# master-v2.net
KiCad netlist of a schematic drawn in EAGLE
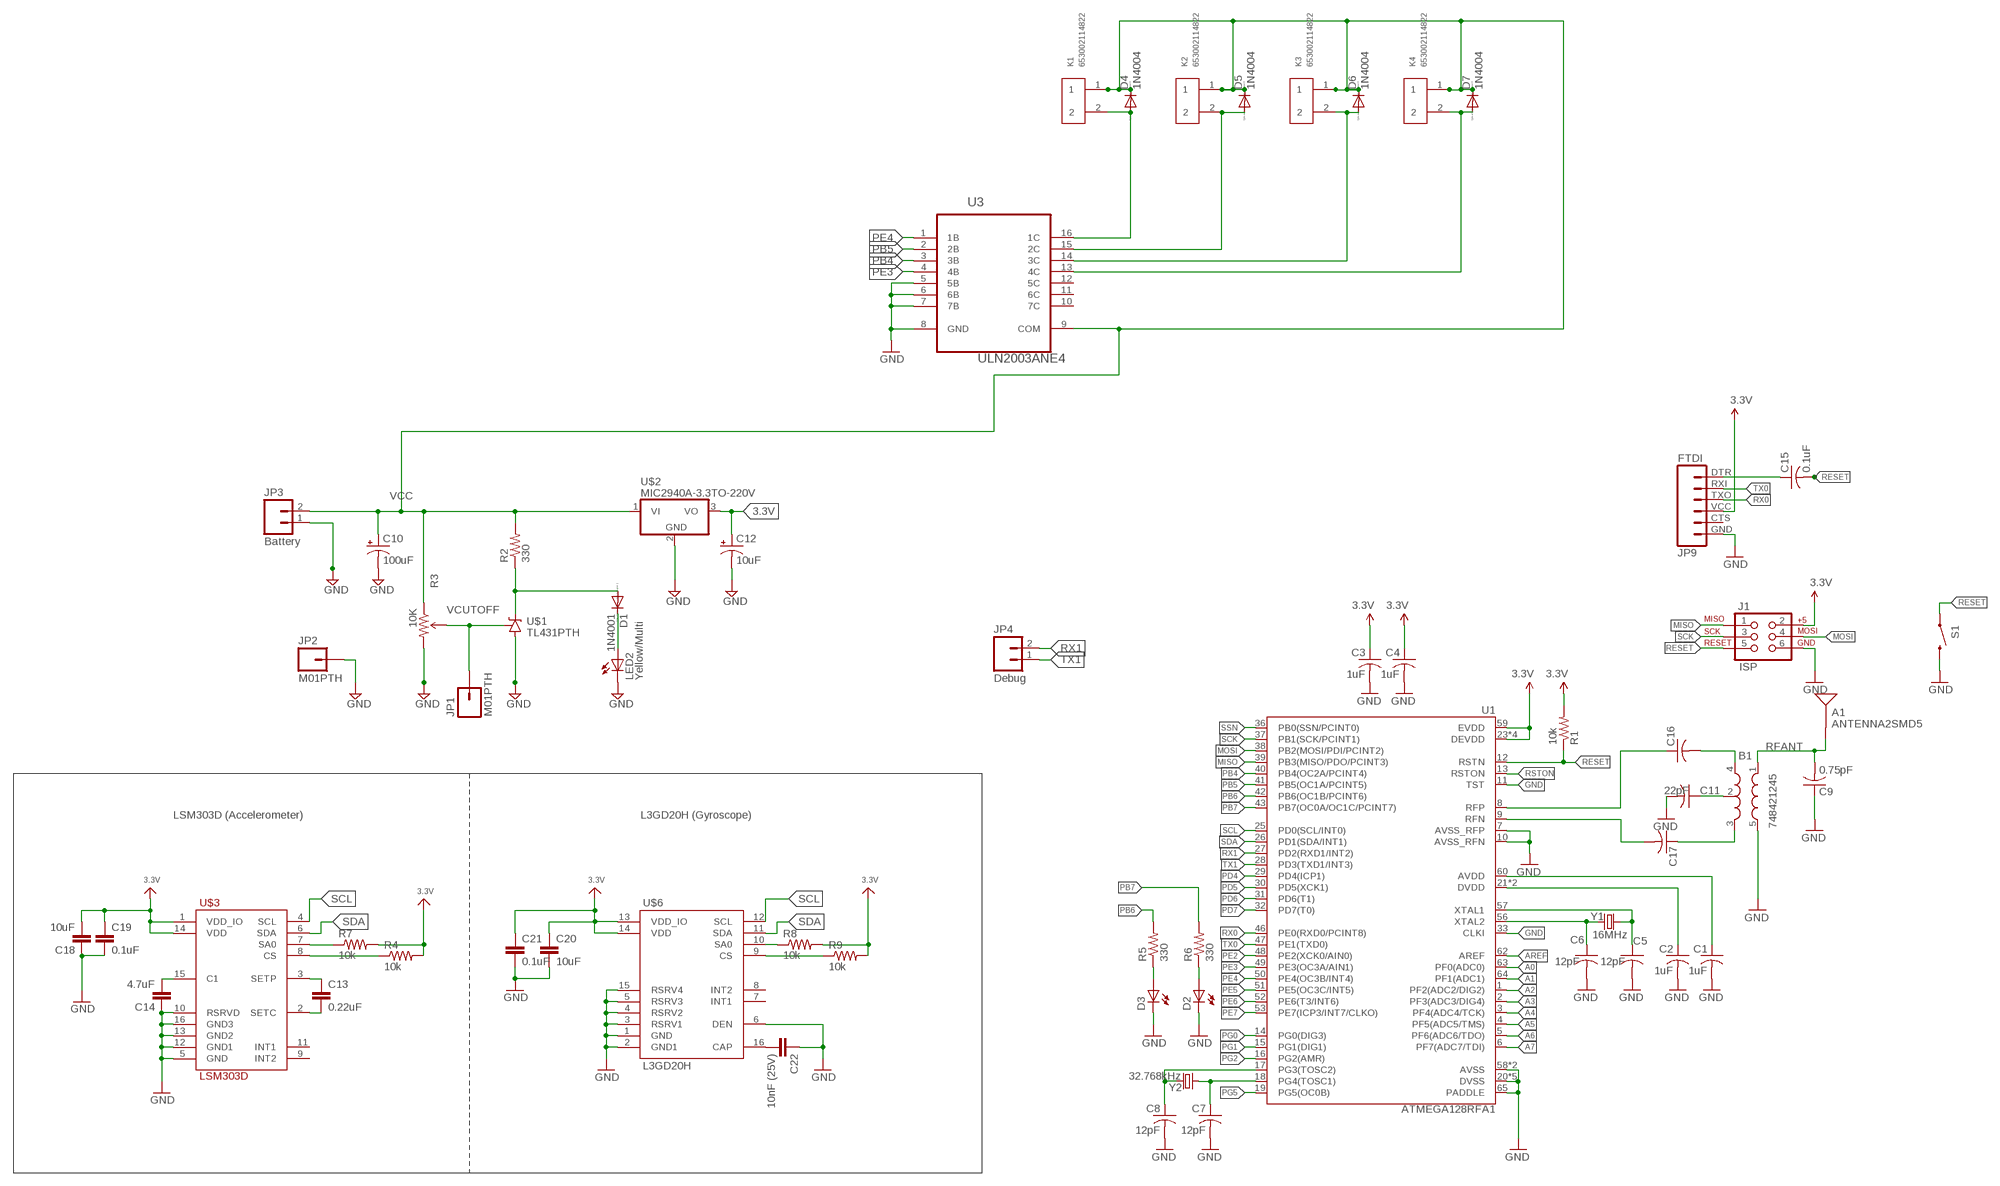
[diagram p0: schematic, sheet 1]

(export (version "E")
  (design (tool "Eeschema 10.0.6"))
  (components
    (comp (ref "A1")
      (value "ANTENNA2SMD5")
      (footprint "eagle-import:ANTENNA-CHIP5")
      (libsource (lib "eagle-import") (part "ANTENNA2SMD5"))
    )
    (comp (ref "B1")
      (value "748421245")
      (footprint "eagle-import:BALUN")
      (libsource (lib "eagle-import") (part "BALUN0805"))
    )
    (comp (ref "C1")
      (value "1uF")
      (footprint "eagle-import:C0805")
      (libsource (lib "eagle-import") (part "C-USC0805"))
    )
    (comp (ref "C2")
      (value "1uF")
      (footprint "eagle-import:C0805")
      (libsource (lib "eagle-import") (part "C-USC0805"))
    )
    (comp (ref "C3")
      (value "1uF")
      (footprint "eagle-import:C0805")
      (libsource (lib "eagle-import") (part "C-USC0805"))
    )
    (comp (ref "C4")
      (value "1uF")
      (footprint "eagle-import:C0805")
      (libsource (lib "eagle-import") (part "C-USC0805"))
    )
    (comp (ref "C5")
      (value "12pF")
      (footprint "eagle-import:C0805")
      (libsource (lib "eagle-import") (part "C-USC0805"))
    )
    (comp (ref "C6")
      (value "12pF")
      (footprint "eagle-import:C0805")
      (libsource (lib "eagle-import") (part "C-USC0805"))
    )
    (comp (ref "C7")
      (value "12pF")
      (footprint "eagle-import:C0805")
      (libsource (lib "eagle-import") (part "C-USC0805"))
    )
    (comp (ref "C8")
      (value "12pF")
      (footprint "eagle-import:C0805")
      (libsource (lib "eagle-import") (part "C-USC0805"))
    )
    (comp (ref "C9")
      (value "0.75pF")
      (footprint "eagle-import:C0805")
      (libsource (lib "eagle-import") (part "C-USC0805"))
    )
    (comp (ref "C10")
      (value "100uF")
      (footprint "eagle-import:E3,5-8")
      (libsource (lib "eagle-import") (part "CPOL-USE3.5-8"))
    )
    (comp (ref "C11")
      (value "22pF")
      (footprint "eagle-import:C0805")
      (libsource (lib "eagle-import") (part "C-USC0805"))
    )
    (comp (ref "C12")
      (value "10uF")
      (footprint "eagle-import:E2,5-5")
      (libsource (lib "eagle-import") (part "CPOL-USE2.5-5"))
    )
    (comp (ref "C13")
      (value "0.22uF")
      (footprint "eagle-import:0805")
      (libsource (lib "eagle-import") (part "CAP0805"))
    )
    (comp (ref "C14")
      (value "4.7uF")
      (footprint "eagle-import:0805")
      (libsource (lib "eagle-import") (part "CAP0805"))
    )
    (comp (ref "C15")
      (value "0.1uF")
      (footprint "eagle-import:C0805")
      (libsource (lib "eagle-import") (part "C-USC0805"))
    )
    (comp (ref "C16")
      (value "C-USC0805")
      (footprint "eagle-import:C0805")
      (libsource (lib "eagle-import") (part "C-USC0805"))
    )
    (comp (ref "C17")
      (value "C-USC0805")
      (footprint "eagle-import:C0805")
      (libsource (lib "eagle-import") (part "C-USC0805"))
    )
    (comp (ref "C18")
      (value "10uF")
      (footprint "eagle-import:0805")
      (libsource (lib "eagle-import") (part "CAP0805"))
    )
    (comp (ref "C19")
      (value "0.1uF")
      (footprint "eagle-import:0805")
      (libsource (lib "eagle-import") (part "CAP0805"))
    )
    (comp (ref "C20")
      (value "10uF")
      (footprint "eagle-import:0805")
      (libsource (lib "eagle-import") (part "CAP0805"))
    )
    (comp (ref "C21")
      (value "0.1uF")
      (footprint "eagle-import:0805")
      (libsource (lib "eagle-import") (part "CAP0805"))
    )
    (comp (ref "C22")
      (value "10nF (25V)")
      (footprint "eagle-import:0805")
      (libsource (lib "eagle-import") (part "CAP0805"))
    )
    (comp (ref "D1")
      (value "1N4001")
      (footprint "eagle-import:DO41-10")
      (libsource (lib "eagle-import") (part "1N4004"))
    )
    (comp (ref "D2")
      (value "LED5MM")
      (footprint "eagle-import:LED5MM")
      (libsource (lib "eagle-import") (part "LED5MM"))
    )
    (comp (ref "D3")
      (value "LED5MM")
      (footprint "eagle-import:LED5MM")
      (libsource (lib "eagle-import") (part "LED5MM"))
    )
    (comp (ref "D4")
      (value "1N4004")
      (footprint "eagle-import:DO41-10")
      (fields (field (name "MF") "NTE ELECTRONICS"))
      (libsource (lib "eagle-import") (part "1N4004"))
    )
    (comp (ref "D5")
      (value "1N4004")
      (footprint "eagle-import:DO41-10")
      (fields (field (name "MF") "NTE ELECTRONICS"))
      (libsource (lib "eagle-import") (part "1N4004"))
    )
    (comp (ref "D6")
      (value "1N4004")
      (footprint "eagle-import:DO41-10")
      (fields (field (name "MF") "NTE ELECTRONICS"))
      (libsource (lib "eagle-import") (part "1N4004"))
    )
    (comp (ref "D7")
      (value "1N4004")
      (footprint "eagle-import:DO41-10")
      (fields (field (name "MF") "NTE ELECTRONICS"))
      (libsource (lib "eagle-import") (part "1N4004"))
    )
    (comp (ref "J1")
      (value "ISP")
      (footprint "eagle-import:2X3-NS")
      (libsource (lib "eagle-import") (part "AVR_SPI_PRG_6NS"))
    )
    (comp (ref "JP1")
      (value "M01PTH")
      (footprint "eagle-import:1X01")
      (libsource (lib "eagle-import") (part "M01PTH"))
    )
    (comp (ref "JP2")
      (value "M01PTH")
      (footprint "eagle-import:1X01")
      (libsource (lib "eagle-import") (part "M01PTH"))
    )
    (comp (ref "JP3")
      (value "Battery")
      (footprint "eagle-import:1X02")
      (libsource (lib "eagle-import") (part "M02PTH"))
    )
    (comp (ref "JP4")
      (value "Debug")
      (footprint "eagle-import:1X02")
      (libsource (lib "eagle-import") (part "M02PTH"))
    )
    (comp (ref "JP9")
      (value "FTDI")
      (footprint "eagle-import:FTDI_BASIC")
      (libsource (lib "eagle-import") (part "FTDI_BASICPTH"))
    )
    (comp (ref "K1")
      (value "653002114822")
      (footprint "eagle-import:653002114822")
      (libsource (lib "eagle-import") (part "653002114822"))
    )
    (comp (ref "K2")
      (value "653002114822")
      (footprint "eagle-import:653002114822")
      (libsource (lib "eagle-import") (part "653002114822"))
    )
    (comp (ref "K3")
      (value "653002114822")
      (footprint "eagle-import:653002114822")
      (libsource (lib "eagle-import") (part "653002114822"))
    )
    (comp (ref "K4")
      (value "653002114822")
      (footprint "eagle-import:653002114822")
      (libsource (lib "eagle-import") (part "653002114822"))
    )
    (comp (ref "LED2")
      (value "Yellow/Multi")
      (footprint "eagle-import:LED5MM")
      (libsource (lib "eagle-import") (part "SparkFun_LED5MM"))
    )
    (comp (ref "R1")
      (value "10k")
      (footprint "eagle-import:R0805")
      (libsource (lib "eagle-import") (part "R-US_R0805"))
    )
    (comp (ref "R2")
      (value "330")
      (footprint "eagle-import:AXIAL-0.3")
      (libsource (lib "eagle-import") (part "RESISTORAXIAL-0.3"))
    )
    (comp (ref "R3")
      (value "10K")
      (footprint "eagle-import:3386U")
      (fields (field (name "CREATOR") "Brandon") (field (name "REVIEWER1") "Chris"))
      (libsource (lib "eagle-import") (part "TRIMPOT-PTH-KNOB"))
    )
    (comp (ref "R4")
      (value "10k")
      (footprint "eagle-import:0805")
      (libsource (lib "eagle-import") (part "SparkFun-Passives_RESISTOR0805-RES"))
    )
    (comp (ref "R5")
      (value "330")
      (footprint "eagle-import:R0805")
      (libsource (lib "eagle-import") (part "R-US_R0805"))
    )
    (comp (ref "R6")
      (value "330")
      (footprint "eagle-import:R0805")
      (libsource (lib "eagle-import") (part "R-US_R0805"))
    )
    (comp (ref "R7")
      (value "10k")
      (footprint "eagle-import:0805")
      (libsource (lib "eagle-import") (part "SparkFun-Passives_RESISTOR0805-RES"))
    )
    (comp (ref "R8")
      (value "10k")
      (footprint "eagle-import:0805")
      (libsource (lib "eagle-import") (part "SparkFun-Passives_RESISTOR0805-RES"))
    )
    (comp (ref "R9")
      (value "10k")
      (footprint "eagle-import:0805")
      (libsource (lib "eagle-import") (part "SparkFun-Passives_RESISTOR0805-RES"))
    )
    (comp (ref "S1")
      (value "SWITCH-MOMENTARY-2SMD")
      (footprint "eagle-import:TACTILE_SWITCH_SMD")
      (libsource (lib "eagle-import") (part "SWITCH-MOMENTARY-2SMD"))
    )
    (comp (ref "U$1")
      (value "TL431PTH")
      (footprint "eagle-import:TO-92")
      (libsource (lib "eagle-import") (part "TL431PTH"))
    )
    (comp (ref "U$2")
      (value "MIC2940A-3.3TO-220V")
      (footprint "eagle-import:TO-220V")
      (libsource (lib "eagle-import") (part "MIC2940A-3.3TO-220V"))
    )
    (comp (ref "U$3")
      (value "LSM303D")
      (footprint "eagle-import:LGA16_3X3MM")
      (libsource (lib "eagle-import") (part "LSM303D"))
    )
    (comp (ref "U$6")
      (value "L3GD20H")
      (footprint "eagle-import:LGA16_3X3MM")
      (libsource (lib "eagle-import") (part "L3GD20H"))
    )
    (comp (ref "U1")
      (value "ATMEGA128RFA1")
      (footprint "eagle-import:QFN-64")
      (libsource (lib "eagle-import") (part "ATMEGA128RFA1"))
    )
    (comp (ref "U3")
      (value "ULN2003ANE4")
      (footprint "eagle-import:DIP254P762X508-16")
      (libsource (lib "eagle-import") (part "ULN2003ANE4"))
    )
    (comp (ref "Y1")
      (value "16MHz")
      (footprint "eagle-import:CRYSTAL-SMD-5X3")
      (libsource (lib "eagle-import") (part "CRYSTAL5X3"))
    )
    (comp (ref "Y2")
      (value "32.768kHz")
      (footprint "eagle-import:CRYSTAL-32KHZ-SMD")
      (libsource (lib "eagle-import") (part "CRYSTAL32-SMD"))
    )
  )
  (nets
    (net (code "1") (name "/RFANT") (class "Default")
      (node (ref "A1") (pin "FEED") (pinfunction "SIGNAL_FEED") (pintype "bidirectional"))
      (node (ref "B1") (pin "1") (pinfunction "IN_1") (pintype "bidirectional"))
      (node (ref "C9") (pin "2") (pinfunction "2_2") (pintype "passive"))
    )
    (net (code "2") (name "/VCC") (class "Default")
      (node (ref "C10") (pin "+") (pinfunction "+_+") (pintype "passive"))
      (node (ref "D4") (pin "C") (pinfunction "C_C") (pintype "passive"))
      (node (ref "D5") (pin "C") (pinfunction "C_C") (pintype "passive"))
      (node (ref "D6") (pin "C") (pinfunction "C_C") (pintype "passive"))
      (node (ref "D7") (pin "C") (pinfunction "C_C") (pintype "passive"))
      (node (ref "JP3") (pin "2") (pinfunction "2_2") (pintype "passive"))
      (node (ref "K1") (pin "1") (pinfunction "1_1") (pintype "bidirectional"))
      (node (ref "K2") (pin "1") (pinfunction "1_1") (pintype "bidirectional"))
      (node (ref "K3") (pin "1") (pinfunction "1_1") (pintype "bidirectional"))
      (node (ref "K4") (pin "1") (pinfunction "1_1") (pintype "bidirectional"))
      (node (ref "R2") (pin "P$2") (pinfunction "2_P$2") (pintype "passive"))
      (node (ref "R3") (pin "1") (pinfunction "CCW_1") (pintype "passive"))
      (node (ref "U$2") (pin "1") (pinfunction "VI_1") (pintype "input"))
      (node (ref "U3") (pin "9") (pinfunction "COM_9") (pintype "output"))
    )
    (net (code "3") (name "/VCUTOFF") (class "Default")
      (node (ref "JP1") (pin "1") (pinfunction "1_1") (pintype "passive"))
      (node (ref "R3") (pin "2") (pinfunction "WIPER_2") (pintype "passive"))
      (node (ref "U$1") (pin "1") (pinfunction "R_1") (pintype "bidirectional"))
    )
    (net (code "4") (name "3.3V") (class "Default")
      (node (ref "C12") (pin "+") (pinfunction "+_+") (pintype "passive"))
      (node (ref "C18") (pin "2") (pinfunction "2_2") (pintype "passive"))
      (node (ref "C19") (pin "1") (pinfunction "1_1") (pintype "passive"))
      (node (ref "C20") (pin "1") (pinfunction "1_1") (pintype "passive"))
      (node (ref "C21") (pin "1") (pinfunction "1_1") (pintype "passive"))
      (node (ref "C3") (pin "1") (pinfunction "1_1") (pintype "passive"))
      (node (ref "C4") (pin "1") (pinfunction "1_1") (pintype "passive"))
      (node (ref "J1") (pin "2") (pinfunction "2_2") (pintype "passive"))
      (node (ref "JP9") (pin "VCC") (pinfunction "4_VCC") (pintype "passive"))
      (node (ref "R1") (pin "2") (pinfunction "2_2") (pintype "passive"))
      (node (ref "R4") (pin "2") (pinfunction "2_2") (pintype "passive"))
      (node (ref "R7") (pin "2") (pinfunction "2_2") (pintype "passive"))
      (node (ref "R8") (pin "2") (pinfunction "2_2") (pintype "passive"))
      (node (ref "R9") (pin "2") (pinfunction "2_2") (pintype "passive"))
      (node (ref "U$2") (pin "3") (pinfunction "VO_3") (pintype "passive"))
      (node (ref "U$3") (pin "1") (pinfunction "VDD_IO_1") (pintype "bidirectional"))
      (node (ref "U$3") (pin "14") (pinfunction "VDD_14") (pintype "bidirectional"))
      (node (ref "U$6") (pin "13") (pinfunction "VDD_IO_13") (pintype "bidirectional"))
      (node (ref "U$6") (pin "14") (pinfunction "VDD_14") (pintype "bidirectional"))
      (node (ref "U1") (pin "23") (pinfunction "DEVDD_23") (pintype "bidirectional"))
      (node (ref "U1") (pin "34") (pinfunction "DEVDD_34") (pintype "bidirectional"))
      (node (ref "U1") (pin "44") (pinfunction "DEVDD_44") (pintype "bidirectional"))
      (node (ref "U1") (pin "54") (pinfunction "DEVDD_54") (pintype "bidirectional"))
      (node (ref "U1") (pin "59") (pinfunction "EVDD_59") (pintype "bidirectional"))
    )
    (net (code "5") (name "A0") (class "Default")
      (node (ref "U1") (pin "63") (pinfunction "PF0(ADC0)_63") (pintype "bidirectional"))
    )
    (net (code "6") (name "A1") (class "Default")
      (node (ref "U1") (pin "64") (pinfunction "PF1(ADC1)_64") (pintype "bidirectional"))
    )
    (net (code "7") (name "A2") (class "Default")
      (node (ref "U1") (pin "1") (pinfunction "PF2(ADC2/DIG2)_1") (pintype "bidirectional"))
    )
    (net (code "8") (name "A3") (class "Default")
      (node (ref "U1") (pin "2") (pinfunction "PF3(ADC3/DIG4)_2") (pintype "bidirectional"))
    )
    (net (code "9") (name "A4") (class "Default")
      (node (ref "U1") (pin "3") (pinfunction "PF4(ADC4/TCK)_3") (pintype "bidirectional"))
    )
    (net (code "10") (name "A5") (class "Default")
      (node (ref "U1") (pin "4") (pinfunction "PF5(ADC5/TMS)_4") (pintype "bidirectional"))
    )
    (net (code "11") (name "A6") (class "Default")
      (node (ref "U1") (pin "5") (pinfunction "PF6(ADC6/TDO)_5") (pintype "bidirectional"))
    )
    (net (code "12") (name "A7") (class "Default")
      (node (ref "U1") (pin "6") (pinfunction "PF7(ADC7/TDI)_6") (pintype "bidirectional"))
    )
    (net (code "13") (name "AREF") (class "Default")
      (node (ref "U1") (pin "62") (pinfunction "AREF_62") (pintype "bidirectional"))
    )
    (net (code "14") (name "GND") (class "Default")
      (node (ref "B1") (pin "5") (pinfunction "GND_5") (pintype "bidirectional"))
      (node (ref "C1") (pin "2") (pinfunction "2_2") (pintype "passive"))
      (node (ref "C10") (pin "-") (pinfunction "-_-") (pintype "passive"))
      (node (ref "C11") (pin "2") (pinfunction "2_2") (pintype "passive"))
      (node (ref "C12") (pin "-") (pinfunction "-_-") (pintype "passive"))
      (node (ref "C14") (pin "1") (pinfunction "1_1") (pintype "passive"))
      (node (ref "C18") (pin "1") (pinfunction "1_1") (pintype "passive"))
      (node (ref "C19") (pin "2") (pinfunction "2_2") (pintype "passive"))
      (node (ref "C2") (pin "2") (pinfunction "2_2") (pintype "passive"))
      (node (ref "C20") (pin "2") (pinfunction "2_2") (pintype "passive"))
      (node (ref "C21") (pin "2") (pinfunction "2_2") (pintype "passive"))
      (node (ref "C22") (pin "1") (pinfunction "1_1") (pintype "passive"))
      (node (ref "C3") (pin "2") (pinfunction "2_2") (pintype "passive"))
      (node (ref "C4") (pin "2") (pinfunction "2_2") (pintype "passive"))
      (node (ref "C5") (pin "2") (pinfunction "2_2") (pintype "passive"))
      (node (ref "C6") (pin "2") (pinfunction "2_2") (pintype "passive"))
      (node (ref "C7") (pin "2") (pinfunction "2_2") (pintype "passive"))
      (node (ref "C8") (pin "2") (pinfunction "2_2") (pintype "passive"))
      (node (ref "C9") (pin "1") (pinfunction "1_1") (pintype "passive"))
      (node (ref "D2") (pin "K") (pinfunction "C_K") (pintype "passive"))
      (node (ref "D3") (pin "K") (pinfunction "C_K") (pintype "passive"))
      (node (ref "J1") (pin "6") (pinfunction "6_6") (pintype "passive"))
      (node (ref "JP2") (pin "1") (pinfunction "1_1") (pintype "passive"))
      (node (ref "JP3") (pin "1") (pinfunction "1_1") (pintype "passive"))
      (node (ref "JP9") (pin "GND") (pinfunction "6_GND") (pintype "passive"))
      (node (ref "LED2") (pin "K") (pinfunction "C_K") (pintype "passive"))
      (node (ref "R3") (pin "3") (pinfunction "CW_3") (pintype "passive"))
      (node (ref "S1") (pin "3") (pinfunction "2_3") (pintype "passive"))
      (node (ref "U$1") (pin "2") (pinfunction "A_2") (pintype "passive"))
      (node (ref "U$2") (pin "2") (pinfunction "GND_2") (pintype "passive"))
      (node (ref "U$3") (pin "10") (pinfunction "RSRVD_10") (pintype "bidirectional"))
      (node (ref "U$3") (pin "12") (pinfunction "GND1_12") (pintype "bidirectional"))
      (node (ref "U$3") (pin "13") (pinfunction "GND2_13") (pintype "bidirectional"))
      (node (ref "U$3") (pin "16") (pinfunction "GND3_16") (pintype "bidirectional"))
      (node (ref "U$3") (pin "5") (pinfunction "GND_5") (pintype "bidirectional"))
      (node (ref "U$6") (pin "1") (pinfunction "GND_1") (pintype "bidirectional"))
      (node (ref "U$6") (pin "15") (pinfunction "RSRV4_15") (pintype "bidirectional"))
      (node (ref "U$6") (pin "2") (pinfunction "GND1_2") (pintype "bidirectional"))
      (node (ref "U$6") (pin "3") (pinfunction "RSRV1_3") (pintype "bidirectional"))
      (node (ref "U$6") (pin "4") (pinfunction "RSRV2_4") (pintype "bidirectional"))
      (node (ref "U$6") (pin "5") (pinfunction "RSRV3_5") (pintype "bidirectional"))
      (node (ref "U$6") (pin "6") (pinfunction "DEN_6") (pintype "bidirectional"))
      (node (ref "U1") (pin "10") (pinfunction "AVSS_RFN_10") (pintype "bidirectional"))
      (node (ref "U1") (pin "11") (pinfunction "TST_11") (pintype "bidirectional"))
      (node (ref "U1") (pin "20") (pinfunction "DVSS_20") (pintype "bidirectional"))
      (node (ref "U1") (pin "24") (pinfunction "DVSS_24") (pintype "bidirectional"))
      (node (ref "U1") (pin "33") (pinfunction "CLKI_33") (pintype "bidirectional"))
      (node (ref "U1") (pin "35") (pinfunction "DVSS_35") (pintype "bidirectional"))
      (node (ref "U1") (pin "45") (pinfunction "DVSS_45") (pintype "bidirectional"))
      (node (ref "U1") (pin "55") (pinfunction "DVSS_55") (pintype "bidirectional"))
      (node (ref "U1") (pin "58") (pinfunction "AVSS_58") (pintype "bidirectional"))
      (node (ref "U1") (pin "61") (pinfunction "AVSS_61") (pintype "bidirectional"))
      (node (ref "U1") (pin "65") (pinfunction "PADDLE_65") (pintype "bidirectional"))
      (node (ref "U1") (pin "7") (pinfunction "AVSS_RFP_7") (pintype "bidirectional"))
      (node (ref "U3") (pin "5") (pinfunction "5B_5") (pintype "input"))
      (node (ref "U3") (pin "6") (pinfunction "6B_6") (pintype "input"))
      (node (ref "U3") (pin "7") (pinfunction "7B_7") (pintype "input"))
      (node (ref "U3") (pin "8") (pinfunction "GND_8") (pintype "passive"))
    )
    (net (code "15") (name "MISO") (class "Default")
      (node (ref "J1") (pin "1") (pinfunction "1_1") (pintype "passive"))
      (node (ref "U1") (pin "39") (pinfunction "PB3(MISO/PDO/PCINT3)_39") (pintype "bidirectional"))
    )
    (net (code "16") (name "MOSI") (class "Default")
      (node (ref "J1") (pin "4") (pinfunction "4_4") (pintype "passive"))
      (node (ref "U1") (pin "38") (pinfunction "PB2(MOSI/PDI/PCINT2)_38") (pintype "bidirectional"))
    )
    (net (code "17") (name "Net-(B1-GND-Pad2)") (class "Default")
      (node (ref "B1") (pin "2") (pinfunction "GND_2") (pintype "bidirectional"))
      (node (ref "C11") (pin "1") (pinfunction "1_1") (pintype "passive"))
    )
    (net (code "18") (name "Net-(B1-OUT1)") (class "Default")
      (node (ref "B1") (pin "4") (pinfunction "OUT1_4") (pintype "bidirectional"))
      (node (ref "C16") (pin "2") (pinfunction "2_2") (pintype "passive"))
    )
    (net (code "19") (name "Net-(B1-OUT2)") (class "Default")
      (node (ref "B1") (pin "3") (pinfunction "OUT2_3") (pintype "bidirectional"))
      (node (ref "C17") (pin "1") (pinfunction "1_1") (pintype "passive"))
    )
    (net (code "20") (name "Net-(C2-Pad1)") (class "Default")
      (node (ref "C2") (pin "1") (pinfunction "1_1") (pintype "passive"))
      (node (ref "U1") (pin "21") (pinfunction "DVDD_21") (pintype "bidirectional"))
      (node (ref "U1") (pin "22") (pinfunction "DVDD_22") (pintype "bidirectional"))
    )
    (net (code "21") (name "Net-(D1-PadC)") (class "Default")
      (node (ref "D1") (pin "C") (pinfunction "C_C") (pintype "passive"))
      (node (ref "LED2") (pin "A") (pinfunction "A_A") (pintype "passive"))
    )
    (net (code "22") (name "Net-(D2-PadA)") (class "Default")
      (node (ref "D2") (pin "A") (pinfunction "A_A") (pintype "passive"))
      (node (ref "R6") (pin "1") (pinfunction "1_1") (pintype "passive"))
    )
    (net (code "23") (name "Net-(D3-PadA)") (class "Default")
      (node (ref "D3") (pin "A") (pinfunction "A_A") (pintype "passive"))
      (node (ref "R5") (pin "1") (pinfunction "1_1") (pintype "passive"))
    )
    (net (code "24") (name "Net-(JP9-1)") (class "Default")
      (node (ref "C15") (pin "1") (pinfunction "1_1") (pintype "passive"))
      (node (ref "JP9") (pin "DTR") (pinfunction "1_DTR") (pintype "passive"))
    )
    (net (code "25") (name "Net-(R2-1)") (class "Default")
      (node (ref "D1") (pin "A") (pinfunction "A_A") (pintype "passive"))
      (node (ref "R2") (pin "P$1") (pinfunction "1_P$1") (pintype "passive"))
      (node (ref "U$1") (pin "3") (pinfunction "C_3") (pintype "passive"))
    )
    (net (code "26") (name "Net-(U$3-C1)") (class "Default")
      (node (ref "C14") (pin "2") (pinfunction "2_2") (pintype "passive"))
      (node (ref "U$3") (pin "15") (pinfunction "C1_15") (pintype "bidirectional"))
    )
    (net (code "27") (name "Net-(U$3-CS)") (class "Default")
      (node (ref "R4") (pin "1") (pinfunction "1_1") (pintype "passive"))
      (node (ref "U$3") (pin "8") (pinfunction "CS_8") (pintype "bidirectional"))
    )
    (net (code "28") (name "Net-(U$3-SA0)") (class "Default")
      (node (ref "R7") (pin "1") (pinfunction "1_1") (pintype "passive"))
      (node (ref "U$3") (pin "7") (pinfunction "SA0_7") (pintype "bidirectional"))
    )
    (net (code "29") (name "Net-(U$3-SETC)") (class "Default")
      (node (ref "C13") (pin "2") (pinfunction "2_2") (pintype "passive"))
      (node (ref "U$3") (pin "2") (pinfunction "SETC_2") (pintype "bidirectional"))
    )
    (net (code "30") (name "Net-(U$3-SETP)") (class "Default")
      (node (ref "C13") (pin "1") (pinfunction "1_1") (pintype "passive"))
      (node (ref "U$3") (pin "3") (pinfunction "SETP_3") (pintype "bidirectional"))
    )
    (net (code "31") (name "Net-(U$6-CAP)") (class "Default")
      (node (ref "C22") (pin "2") (pinfunction "2_2") (pintype "passive"))
      (node (ref "U$6") (pin "16") (pinfunction "CAP_16") (pintype "bidirectional"))
    )
    (net (code "32") (name "Net-(U$6-CS)") (class "Default")
      (node (ref "R9") (pin "1") (pinfunction "1_1") (pintype "passive"))
      (node (ref "U$6") (pin "9") (pinfunction "CS_9") (pintype "bidirectional"))
    )
    (net (code "33") (name "Net-(U$6-SA0)") (class "Default")
      (node (ref "R8") (pin "1") (pinfunction "1_1") (pintype "passive"))
      (node (ref "U$6") (pin "10") (pinfunction "SA0_10") (pintype "bidirectional"))
    )
    (net (code "34") (name "Net-(U1-AVDD)") (class "Default")
      (node (ref "C1") (pin "1") (pinfunction "1_1") (pintype "passive"))
      (node (ref "U1") (pin "60") (pinfunction "AVDD_60") (pintype "bidirectional"))
    )
    (net (code "35") (name "Net-(U1-PG3(TOSC2))") (class "Default")
      (node (ref "C8") (pin "1") (pinfunction "1_1") (pintype "passive"))
      (node (ref "U1") (pin "17") (pinfunction "PG3(TOSC2)_17") (pintype "bidirectional"))
      (node (ref "Y2") (pin "X2") (pinfunction "2_X2") (pintype "passive"))
    )
    (net (code "36") (name "Net-(U1-PG4(TOSC1))") (class "Default")
      (node (ref "C7") (pin "1") (pinfunction "1_1") (pintype "passive"))
      (node (ref "U1") (pin "18") (pinfunction "PG4(TOSC1)_18") (pintype "bidirectional"))
      (node (ref "Y2") (pin "X1") (pinfunction "1_X1") (pintype "passive"))
    )
    (net (code "37") (name "Net-(U1-RFN)") (class "Default")
      (node (ref "C17") (pin "2") (pinfunction "2_2") (pintype "passive"))
      (node (ref "U1") (pin "9") (pinfunction "RFN_9") (pintype "bidirectional"))
    )
    (net (code "38") (name "Net-(U1-RFP)") (class "Default")
      (node (ref "C16") (pin "1") (pinfunction "1_1") (pintype "passive"))
      (node (ref "U1") (pin "8") (pinfunction "RFP_8") (pintype "bidirectional"))
    )
    (net (code "39") (name "Net-(U1-XTAL1)") (class "Default")
      (node (ref "C5") (pin "1") (pinfunction "1_1") (pintype "passive"))
      (node (ref "U1") (pin "57") (pinfunction "XTAL1_57") (pintype "bidirectional"))
      (node (ref "Y1") (pin "3") (pinfunction "2_3") (pintype "passive"))
    )
    (net (code "40") (name "Net-(U1-XTAL2)") (class "Default")
      (node (ref "C6") (pin "1") (pinfunction "1_1") (pintype "passive"))
      (node (ref "U1") (pin "56") (pinfunction "XTAL2_56") (pintype "bidirectional"))
      (node (ref "Y1") (pin "1") (pinfunction "1_1") (pintype "passive"))
    )
    (net (code "41") (name "Net-(U3-1C)") (class "Default")
      (node (ref "D4") (pin "A") (pinfunction "A_A") (pintype "passive"))
      (node (ref "K1") (pin "2") (pinfunction "2_2") (pintype "bidirectional"))
      (node (ref "U3") (pin "16") (pinfunction "1C_16") (pintype "output"))
    )
    (net (code "42") (name "Net-(U3-2C)") (class "Default")
      (node (ref "D5") (pin "A") (pinfunction "A_A") (pintype "passive"))
      (node (ref "K2") (pin "2") (pinfunction "2_2") (pintype "bidirectional"))
      (node (ref "U3") (pin "15") (pinfunction "2C_15") (pintype "output"))
    )
    (net (code "43") (name "Net-(U3-3C)") (class "Default")
      (node (ref "D6") (pin "A") (pinfunction "A_A") (pintype "passive"))
      (node (ref "K3") (pin "2") (pinfunction "2_2") (pintype "bidirectional"))
      (node (ref "U3") (pin "14") (pinfunction "3C_14") (pintype "output"))
    )
    (net (code "44") (name "Net-(U3-4C)") (class "Default")
      (node (ref "D7") (pin "A") (pinfunction "A_A") (pintype "passive"))
      (node (ref "K4") (pin "2") (pinfunction "2_2") (pintype "bidirectional"))
      (node (ref "U3") (pin "13") (pinfunction "4C_13") (pintype "output"))
    )
    (net (code "45") (name "PB4") (class "Default")
      (node (ref "U1") (pin "40") (pinfunction "PB4(OC2A/PCINT4)_40") (pintype "bidirectional"))
      (node (ref "U3") (pin "3") (pinfunction "3B_3") (pintype "input"))
    )
    (net (code "46") (name "PB5") (class "Default")
      (node (ref "U1") (pin "41") (pinfunction "PB5(OC1A/PCINT5)_41") (pintype "bidirectional"))
      (node (ref "U3") (pin "2") (pinfunction "2B_2") (pintype "input"))
    )
    (net (code "47") (name "PB6") (class "Default")
      (node (ref "R5") (pin "2") (pinfunction "2_2") (pintype "passive"))
      (node (ref "U1") (pin "42") (pinfunction "PB6(OC1B/PCINT6)_42") (pintype "bidirectional"))
    )
    (net (code "48") (name "PB7") (class "Default")
      (node (ref "R6") (pin "2") (pinfunction "2_2") (pintype "passive"))
      (node (ref "U1") (pin "43") (pinfunction "PB7(OC0A/OC1C/PCINT7)_43") (pintype "bidirectional"))
    )
    (net (code "49") (name "PD4") (class "Default")
      (node (ref "U1") (pin "29") (pinfunction "PD4(ICP1)_29") (pintype "bidirectional"))
    )
    (net (code "50") (name "PD5") (class "Default")
      (node (ref "U1") (pin "30") (pinfunction "PD5(XCK1)_30") (pintype "bidirectional"))
    )
    (net (code "51") (name "PD6") (class "Default")
      (node (ref "U1") (pin "31") (pinfunction "PD6(T1)_31") (pintype "bidirectional"))
    )
    (net (code "52") (name "PD7") (class "Default")
      (node (ref "U1") (pin "32") (pinfunction "PD7(T0)_32") (pintype "bidirectional"))
    )
    (net (code "53") (name "PE2") (class "Default")
      (node (ref "U1") (pin "48") (pinfunction "PE2(XCK0/AIN0)_48") (pintype "bidirectional"))
    )
    (net (code "54") (name "PE3") (class "Default")
      (node (ref "U1") (pin "49") (pinfunction "PE3(OC3A/AIN1)_49") (pintype "bidirectional"))
      (node (ref "U3") (pin "4") (pinfunction "4B_4") (pintype "input"))
    )
    (net (code "55") (name "PE4") (class "Default")
      (node (ref "U1") (pin "50") (pinfunction "PE4(OC3B/INT4)_50") (pintype "bidirectional"))
      (node (ref "U3") (pin "1") (pinfunction "1B_1") (pintype "input"))
    )
    (net (code "56") (name "PE5") (class "Default")
      (node (ref "U1") (pin "51") (pinfunction "PE5(OC3C/INT5)_51") (pintype "bidirectional"))
    )
    (net (code "57") (name "PE6") (class "Default")
      (node (ref "U1") (pin "52") (pinfunction "PE6(T3/INT6)_52") (pintype "bidirectional"))
    )
    (net (code "58") (name "PE7") (class "Default")
      (node (ref "U1") (pin "53") (pinfunction "PE7(ICP3/INT7/CLKO)_53") (pintype "bidirectional"))
    )
    (net (code "59") (name "PG0") (class "Default")
      (node (ref "U1") (pin "14") (pinfunction "PG0(DIG3)_14") (pintype "bidirectional"))
    )
    (net (code "60") (name "PG1") (class "Default")
      (node (ref "U1") (pin "15") (pinfunction "PG1(DIG1)_15") (pintype "bidirectional"))
    )
    (net (code "61") (name "PG2") (class "Default")
      (node (ref "U1") (pin "16") (pinfunction "PG2(AMR)_16") (pintype "bidirectional"))
    )
    (net (code "62") (name "PG5") (class "Default")
      (node (ref "U1") (pin "19") (pinfunction "PG5(OC0B)_19") (pintype "bidirectional"))
    )
    (net (code "63") (name "RESET") (class "Default")
      (node (ref "C15") (pin "2") (pinfunction "2_2") (pintype "passive"))
      (node (ref "J1") (pin "5") (pinfunction "5_5") (pintype "passive"))
      (node (ref "R1") (pin "1") (pinfunction "1_1") (pintype "passive"))
      (node (ref "S1") (pin "1") (pinfunction "1_1") (pintype "passive"))
      (node (ref "U1") (pin "12") (pinfunction "RSTN_12") (pintype "bidirectional"))
    )
    (net (code "64") (name "RSTON") (class "Default")
      (node (ref "U1") (pin "13") (pinfunction "RSTON_13") (pintype "bidirectional"))
    )
    (net (code "65") (name "RX0") (class "Default")
      (node (ref "JP9") (pin "TXO") (pinfunction "3_TXO") (pintype "passive"))
      (node (ref "U1") (pin "46") (pinfunction "PE0(RXD0/PCINT8)_46") (pintype "bidirectional"))
    )
    (net (code "66") (name "RX1") (class "Default")
      (node (ref "JP4") (pin "2") (pinfunction "2_2") (pintype "passive"))
      (node (ref "U1") (pin "27") (pinfunction "PD2(RXD1/INT2)_27") (pintype "bidirectional"))
    )
    (net (code "67") (name "SCK") (class "Default")
      (node (ref "J1") (pin "3") (pinfunction "3_3") (pintype "passive"))
      (node (ref "U1") (pin "37") (pinfunction "PB1(SCK/PCINT1)_37") (pintype "bidirectional"))
    )
    (net (code "68") (name "SCL") (class "Default")
      (node (ref "U$3") (pin "4") (pinfunction "SCL_4") (pintype "bidirectional"))
      (node (ref "U$6") (pin "12") (pinfunction "SCL_12") (pintype "bidirectional"))
      (node (ref "U1") (pin "25") (pinfunction "PD0(SCL/INT0)_25") (pintype "bidirectional"))
    )
    (net (code "69") (name "SDA") (class "Default")
      (node (ref "U$3") (pin "6") (pinfunction "SDA_6") (pintype "bidirectional"))
      (node (ref "U$6") (pin "11") (pinfunction "SDA_11") (pintype "bidirectional"))
      (node (ref "U1") (pin "26") (pinfunction "PD1(SDA/INT1)_26") (pintype "bidirectional"))
    )
    (net (code "70") (name "SSN") (class "Default")
      (node (ref "U1") (pin "36") (pinfunction "PB0(SSN/PCINT0)_36") (pintype "bidirectional"))
    )
    (net (code "71") (name "TX0") (class "Default")
      (node (ref "JP9") (pin "RXI") (pinfunction "2_RXI") (pintype "passive"))
      (node (ref "U1") (pin "47") (pinfunction "PE1(TXD0)_47") (pintype "bidirectional"))
    )
    (net (code "72") (name "TX1") (class "Default")
      (node (ref "JP4") (pin "1") (pinfunction "1_1") (pintype "passive"))
      (node (ref "U1") (pin "28") (pinfunction "PD3(TXD1/INT3)_28") (pintype "bidirectional"))
    )
    (net (code "73") (name "unconnected-(JP9-5-PadCTS)") (class "Default")
      (node (ref "JP9") (pin "CTS") (pinfunction "5_CTS") (pintype "passive"))
    )
    (net (code "74") (name "unconnected-(U$3-INT1-Pad11)") (class "Default")
      (node (ref "U$3") (pin "11") (pinfunction "INT1_11") (pintype "bidirectional"))
    )
    (net (code "75") (name "unconnected-(U$3-INT2-Pad9)") (class "Default")
      (node (ref "U$3") (pin "9") (pinfunction "INT2_9") (pintype "bidirectional"))
    )
    (net (code "76") (name "unconnected-(U$6-INT1-Pad7)") (class "Default")
      (node (ref "U$6") (pin "7") (pinfunction "INT1_7") (pintype "bidirectional"))
    )
    (net (code "77") (name "unconnected-(U$6-INT2-Pad8)") (class "Default")
      (node (ref "U$6") (pin "8") (pinfunction "INT2_8") (pintype "bidirectional"))
    )
    (net (code "78") (name "unconnected-(U3-5C-Pad12)") (class "Default")
      (node (ref "U3") (pin "12") (pinfunction "5C_12") (pintype "output"))
    )
    (net (code "79") (name "unconnected-(U3-6C-Pad11)") (class "Default")
      (node (ref "U3") (pin "11") (pinfunction "6C_11") (pintype "output"))
    )
    (net (code "80") (name "unconnected-(U3-7C-Pad10)") (class "Default")
      (node (ref "U3") (pin "10") (pinfunction "7C_10") (pintype "output"))
    )
  )
)
